# SPres.net
KiCad netlist of a schematic drawn in Altium Designer
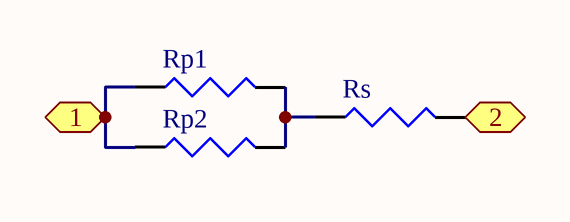
[diagram p0: SPres.SchDoc]

(export (version "E")
  (design (tool "Eeschema 10.0.6"))
  (components
    (comp (ref "Rp1")
      (value "es3")
      (footprint "RES400")
      (description "Resistor")
      (fields (field (name "PUBLISHER") "Altium Limited"))
      (libsource (lib "LIBEBAL") (part "Res3"))
    )
    (comp (ref "Rp2")
      (value "es3")
      (footprint "RES400")
      (description "Resistor")
      (fields (field (name "PUBLISHER") "Altium Limited"))
      (libsource (lib "LIBEBAL") (part "Res3"))
    )
    (comp (ref "Rs")
      (value "es3")
      (footprint "RES400")
      (description "Resistor")
      (fields (field (name "PUBLISHER") "Altium Limited"))
      (libsource (lib "LIBEBAL") (part "Res3"))
    )
  )
  (nets
    (net (code "1") (name "/1") (class "Default")
      (node (ref "Rp1") (pin "1") (pinfunction "1_1") (pintype "passive"))
      (node (ref "Rp2") (pin "1") (pinfunction "1_1") (pintype "passive"))
    )
    (net (code "2") (name "/2") (class "Default")
      (node (ref "Rs") (pin "2") (pinfunction "2_2") (pintype "passive"))
    )
    (net (code "3") (name "Net-(Rp1-Pad2)") (class "Default")
      (node (ref "Rp1") (pin "2") (pinfunction "2_2") (pintype "passive"))
      (node (ref "Rp2") (pin "2") (pinfunction "2_2") (pintype "passive"))
      (node (ref "Rs") (pin "1") (pinfunction "1_1") (pintype "passive"))
    )
  )
)
